# Blinds_Motor_ESP32.net
KiCad netlist of a schematic drawn in EAGLE
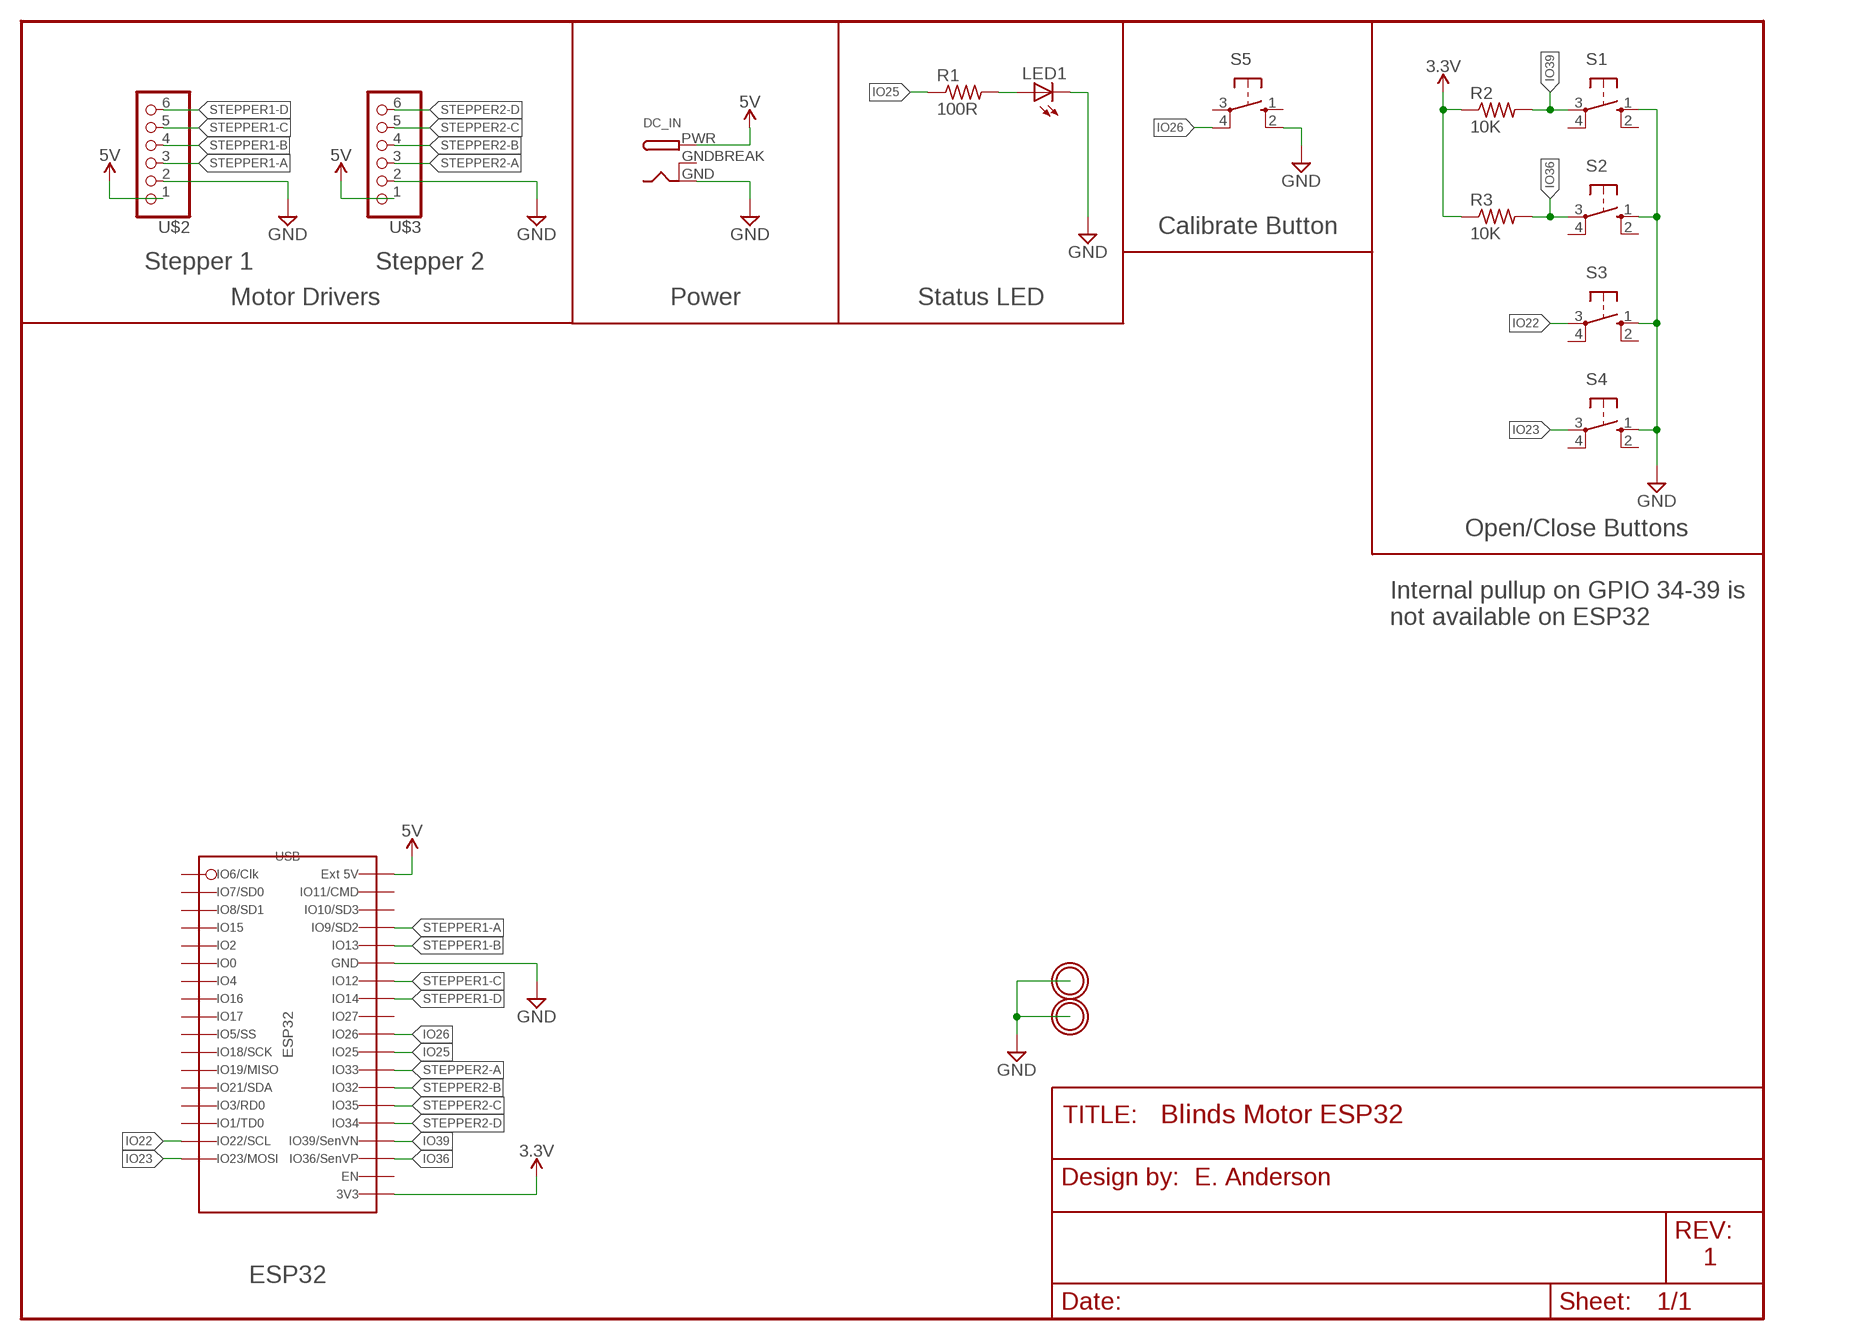
[diagram p0: schematic, sheet 1]

(export (version "E")
  (design (tool "Eeschema 10.0.6"))
  (components
    (comp (ref "DC_IN")
      (value "DCBARRELPTH")
      (footprint "eagle-import:DCJACK_2MM_PTH")
      (libsource (lib "eagle-import") (part "DCBARRELPTH"))
    )
    (comp (ref "LED1")
      (value "LED-CHIPLED_1206_LONG")
      (footprint "eagle-import:CHIPLED_1206_LONG")
      (libsource (lib "eagle-import") (part "LED-CHIPLED_1206_LONG"))
    )
    (comp (ref "R1")
      (value "100R")
      (footprint "eagle-import:R1206")
      (libsource (lib "eagle-import") (part "R_USR1206"))
    )
    (comp (ref "R2")
      (value "10K")
      (footprint "eagle-import:R1206")
      (libsource (lib "eagle-import") (part "R_USR1206"))
    )
    (comp (ref "R3")
      (value "10K")
      (footprint "eagle-import:R1206")
      (libsource (lib "eagle-import") (part "R_USR1206"))
    )
    (comp (ref "S1")
      (value "B3F-10XX")
      (footprint "eagle-import:B3F-10XX")
      (fields (field (name "MPN") "B3F-1000"))
      (libsource (lib "eagle-import") (part "B3F-10XX"))
    )
    (comp (ref "S2")
      (value "B3F-10XX")
      (footprint "eagle-import:B3F-10XX")
      (fields (field (name "MPN") "B3F-1000"))
      (libsource (lib "eagle-import") (part "B3F-10XX"))
    )
    (comp (ref "S3")
      (value "B3F-10XX")
      (footprint "eagle-import:B3F-10XX")
      (fields (field (name "MPN") "B3F-1000"))
      (libsource (lib "eagle-import") (part "B3F-10XX"))
    )
    (comp (ref "S4")
      (value "B3F-10XX")
      (footprint "eagle-import:B3F-10XX")
      (fields (field (name "MPN") "B3F-1000"))
      (libsource (lib "eagle-import") (part "B3F-10XX"))
    )
    (comp (ref "S5")
      (value "B3F-10XX")
      (footprint "eagle-import:B3F-10XX")
      (fields (field (name "MPN") "B3F-1000"))
      (libsource (lib "eagle-import") (part "B3F-10XX"))
    )
    (comp (ref "U$2")
      (value "Stepper 1")
      (footprint "eagle-import:1X06")
      (libsource (lib "eagle-import") (part "1X6_HEADER_LONG"))
    )
    (comp (ref "U$3")
      (value "Stepper 2")
      (footprint "eagle-import:1X06")
      (libsource (lib "eagle-import") (part "1X6_HEADER_LONG"))
    )
    (comp (ref "U$5")
      (value "MICROBUILDER_MOUNTINGHOLE3.0THIN")
      (footprint "eagle-import:MICROBUILDER_MOUNTINGHOLE_3.0_PLATEDTHIN")
      (libsource (lib "eagle-import") (part "MICROBUILDER_MOUNTINGHOLE3.0THIN"))
    )
    (comp (ref "U$6")
      (value "MICROBUILDER_MOUNTINGHOLE3.0THIN")
      (footprint "eagle-import:MICROBUILDER_MOUNTINGHOLE_3.0_PLATEDTHIN")
      (libsource (lib "eagle-import") (part "MICROBUILDER_MOUNTINGHOLE3.0THIN"))
    )
    (comp (ref "U$7")
      (value "ESP32-DEV")
      (footprint "eagle-import:ESP32_DEV")
      (libsource (lib "eagle-import") (part "ESP32-DEV"))
    )
  )
  (nets
    (net (code "1") (name "/GNDBREAK") (class "Default")
      (node (ref "DC_IN") (pin "GNDBREAK") (pinfunction "GNDBREAK_GNDBREAK") (pintype "power_in"))
    )
    (net (code "2") (name "3.3V") (class "Default")
      (node (ref "R2") (pin "1") (pinfunction "1_1") (pintype "passive"))
      (node (ref "R3") (pin "1") (pinfunction "1_1") (pintype "passive"))
      (node (ref "U$7") (pin "3V3") (pinfunction "3V3_3V3") (pintype "power_in"))
    )
    (net (code "3") (name "5V") (class "Default")
      (node (ref "DC_IN") (pin "PWR") (pinfunction "PWR_PWR") (pintype "power_in"))
      (node (ref "U$2") (pin "1") (pinfunction "1_1") (pintype "passive"))
      (node (ref "U$3") (pin "1") (pinfunction "1_1") (pintype "passive"))
      (node (ref "U$7") (pin "5V") (pinfunction "EXT_5V_5V") (pintype "power_in"))
    )
    (net (code "4") (name "GND") (class "Default")
      (node (ref "DC_IN") (pin "GND") (pinfunction "GND_GND") (pintype "power_in"))
      (node (ref "LED1") (pin "C") (pinfunction "C_C") (pintype "passive"))
      (node (ref "S1") (pin "1") (pinfunction "S_1") (pintype "passive"))
      (node (ref "S2") (pin "1") (pinfunction "S_1") (pintype "passive"))
      (node (ref "S3") (pin "1") (pinfunction "S_1") (pintype "passive"))
      (node (ref "S4") (pin "1") (pinfunction "S_1") (pintype "passive"))
      (node (ref "S5") (pin "2") (pinfunction "S1_2") (pintype "passive"))
      (node (ref "U$2") (pin "2") (pinfunction "2_2") (pintype "passive"))
      (node (ref "U$3") (pin "2") (pinfunction "2_2") (pintype "passive"))
      (node (ref "U$7") (pin "GND") (pinfunction "GND1_GND") (pintype "bidirectional"))
      (node (ref "U$7") (pin "GND1") (pinfunction "GND1_GND1") (pintype "bidirectional"))
      (node (ref "U$7") (pin "GND2") (pinfunction "GND1_GND2") (pintype "bidirectional"))
    )
    (net (code "5") (name "IO22") (class "Default")
      (node (ref "S3") (pin "3") (pinfunction "P_3") (pintype "passive"))
      (node (ref "U$7") (pin "IO22") (pinfunction "IO22_IO22") (pintype "bidirectional"))
    )
    (net (code "6") (name "IO23") (class "Default")
      (node (ref "S4") (pin "3") (pinfunction "P_3") (pintype "passive"))
      (node (ref "U$7") (pin "IO23") (pinfunction "IO23/SCL_IO23") (pintype "bidirectional"))
    )
    (net (code "7") (name "IO25") (class "Default")
      (node (ref "R1") (pin "1") (pinfunction "1_1") (pintype "passive"))
      (node (ref "U$7") (pin "IO25") (pinfunction "IO25_IO25") (pintype "bidirectional"))
    )
    (net (code "8") (name "IO26") (class "Default")
      (node (ref "S5") (pin "4") (pinfunction "P1_4") (pintype "passive"))
      (node (ref "U$7") (pin "IO26") (pinfunction "IO26_IO26") (pintype "bidirectional"))
    )
    (net (code "9") (name "IO36") (class "Default")
      (node (ref "R3") (pin "2") (pinfunction "2_2") (pintype "passive"))
      (node (ref "S2") (pin "3") (pinfunction "P_3") (pintype "passive"))
      (node (ref "U$7") (pin "IO36-SVP") (pinfunction "IO36/SVP_IO36-SVP") (pintype "bidirectional"))
    )
    (net (code "10") (name "IO39") (class "Default")
      (node (ref "R2") (pin "2") (pinfunction "2_2") (pintype "passive"))
      (node (ref "S1") (pin "3") (pinfunction "P_3") (pintype "passive"))
      (node (ref "U$7") (pin "IO39-SVN") (pinfunction "IO39/SVN_IO39-SVN") (pintype "bidirectional"))
    )
    (net (code "11") (name "Net-(LED1-PadA)") (class "Default")
      (node (ref "LED1") (pin "A") (pinfunction "A_A") (pintype "passive"))
      (node (ref "R1") (pin "2") (pinfunction "2_2") (pintype "passive"))
    )
    (net (code "12") (name "STEPPER1-A") (class "Default")
      (node (ref "U$2") (pin "3") (pinfunction "3_3") (pintype "passive"))
      (node (ref "U$7") (pin "IO9-SD2") (pinfunction "IO9/SD2_IO9-SD2") (pintype "bidirectional"))
    )
    (net (code "13") (name "STEPPER1-B") (class "Default")
      (node (ref "U$2") (pin "4") (pinfunction "4_4") (pintype "passive"))
      (node (ref "U$7") (pin "IO13") (pinfunction "IO13_IO13") (pintype "bidirectional"))
    )
    (net (code "14") (name "STEPPER1-C") (class "Default")
      (node (ref "U$2") (pin "5") (pinfunction "5_5") (pintype "passive"))
      (node (ref "U$7") (pin "IO12") (pinfunction "IO12_IO12") (pintype "bidirectional"))
    )
    (net (code "15") (name "STEPPER1-D") (class "Default")
      (node (ref "U$2") (pin "6") (pinfunction "6_6") (pintype "passive"))
      (node (ref "U$7") (pin "IO14") (pinfunction "IO14_IO14") (pintype "bidirectional"))
    )
    (net (code "16") (name "STEPPER2-A") (class "Default")
      (node (ref "U$3") (pin "3") (pinfunction "3_3") (pintype "passive"))
      (node (ref "U$7") (pin "IO33") (pinfunction "IO33_IO33") (pintype "bidirectional"))
    )
    (net (code "17") (name "STEPPER2-B") (class "Default")
      (node (ref "U$3") (pin "4") (pinfunction "4_4") (pintype "passive"))
      (node (ref "U$7") (pin "IO32") (pinfunction "IO32_IO32") (pintype "bidirectional"))
    )
    (net (code "18") (name "STEPPER2-C") (class "Default")
      (node (ref "U$3") (pin "5") (pinfunction "5_5") (pintype "passive"))
      (node (ref "U$7") (pin "IO35") (pinfunction "IO35_IO35") (pintype "bidirectional"))
    )
    (net (code "19") (name "STEPPER2-D") (class "Default")
      (node (ref "U$3") (pin "6") (pinfunction "6_6") (pintype "passive"))
      (node (ref "U$7") (pin "IO34") (pinfunction "IO34_IO34") (pintype "bidirectional"))
    )
    (net (code "20") (name "unconnected-(S1-P1-Pad4)") (class "Default")
      (node (ref "S1") (pin "4") (pinfunction "P1_4") (pintype "passive"))
    )
    (net (code "21") (name "unconnected-(S1-S1-Pad2)") (class "Default")
      (node (ref "S1") (pin "2") (pinfunction "S1_2") (pintype "passive"))
    )
    (net (code "22") (name "unconnected-(S2-P1-Pad4)") (class "Default")
      (node (ref "S2") (pin "4") (pinfunction "P1_4") (pintype "passive"))
    )
    (net (code "23") (name "unconnected-(S2-S1-Pad2)") (class "Default")
      (node (ref "S2") (pin "2") (pinfunction "S1_2") (pintype "passive"))
    )
    (net (code "24") (name "unconnected-(S3-P1-Pad4)") (class "Default")
      (node (ref "S3") (pin "4") (pinfunction "P1_4") (pintype "passive"))
    )
    (net (code "25") (name "unconnected-(S3-S1-Pad2)") (class "Default")
      (node (ref "S3") (pin "2") (pinfunction "S1_2") (pintype "passive"))
    )
    (net (code "26") (name "unconnected-(S4-P1-Pad4)") (class "Default")
      (node (ref "S4") (pin "4") (pinfunction "P1_4") (pintype "passive"))
    )
    (net (code "27") (name "unconnected-(S4-S1-Pad2)") (class "Default")
      (node (ref "S4") (pin "2") (pinfunction "S1_2") (pintype "passive"))
    )
    (net (code "28") (name "unconnected-(S5-P-Pad3)") (class "Default")
      (node (ref "S5") (pin "3") (pinfunction "P_3") (pintype "passive"))
    )
    (net (code "29") (name "unconnected-(S5-S-Pad1)") (class "Default")
      (node (ref "S5") (pin "1") (pinfunction "S_1") (pintype "passive"))
    )
    (net (code "30") (name "unconnected-(U$7-CLK-PadIO6-CLK)") (class "Default")
      (node (ref "U$7") (pin "IO6-CLK") (pinfunction "CLK_IO6-CLK") (pintype "bidirectional"))
    )
    (net (code "31") (name "unconnected-(U$7-IO10{slash}SD3-PadIO10-SD3)") (class "Default")
      (node (ref "U$7") (pin "IO10-SD3") (pinfunction "IO10/SD3_IO10-SD3") (pintype "bidirectional"))
    )
    (net (code "32") (name "unconnected-(U$7-IO11{slash}CMD-PadIO11-CMD)") (class "Default")
      (node (ref "U$7") (pin "IO11-CMD") (pinfunction "IO11/CMD_IO11-CMD") (pintype "bidirectional"))
    )
    (net (code "33") (name "unconnected-(U$7-IO21{slash}SDA-PadIO21)") (class "Default")
      (node (ref "U$7") (pin "IO21") (pinfunction "IO21/SDA_IO21") (pintype "bidirectional"))
    )
    (net (code "34") (name "unconnected-(U$7-PadEN)") (class "Default")
      (node (ref "U$7") (pin "EN") (pinfunction "EN_EN") (pintype "bidirectional"))
    )
    (net (code "35") (name "unconnected-(U$7-PadIO0)") (class "Default")
      (node (ref "U$7") (pin "IO0") (pinfunction "IO0_IO0") (pintype "bidirectional"))
    )
    (net (code "36") (name "unconnected-(U$7-PadIO2)") (class "Default")
      (node (ref "U$7") (pin "IO2") (pinfunction "IO2_IO2") (pintype "bidirectional"))
    )
    (net (code "37") (name "unconnected-(U$7-PadIO4)") (class "Default")
      (node (ref "U$7") (pin "IO4") (pinfunction "IO4_IO4") (pintype "bidirectional"))
    )
    (net (code "38") (name "unconnected-(U$7-PadIO5)") (class "Default")
      (node (ref "U$7") (pin "IO5") (pinfunction "IO5_IO5") (pintype "bidirectional"))
    )
    (net (code "39") (name "unconnected-(U$7-PadIO15)") (class "Default")
      (node (ref "U$7") (pin "IO15") (pinfunction "IO15_IO15") (pintype "bidirectional"))
    )
    (net (code "40") (name "unconnected-(U$7-PadIO16)") (class "Default")
      (node (ref "U$7") (pin "IO16") (pinfunction "IO16_IO16") (pintype "bidirectional"))
    )
    (net (code "41") (name "unconnected-(U$7-PadIO17)") (class "Default")
      (node (ref "U$7") (pin "IO17") (pinfunction "IO17_IO17") (pintype "bidirectional"))
    )
    (net (code "42") (name "unconnected-(U$7-PadIO18)") (class "Default")
      (node (ref "U$7") (pin "IO18") (pinfunction "IO18_IO18") (pintype "bidirectional"))
    )
    (net (code "43") (name "unconnected-(U$7-PadIO19)") (class "Default")
      (node (ref "U$7") (pin "IO19") (pinfunction "IO19_IO19") (pintype "bidirectional"))
    )
    (net (code "44") (name "unconnected-(U$7-PadIO27)") (class "Default")
      (node (ref "U$7") (pin "IO27") (pinfunction "IO27_IO27") (pintype "bidirectional"))
    )
    (net (code "45") (name "unconnected-(U$7-RXD0-PadIO3-RXD0)") (class "Default")
      (node (ref "U$7") (pin "IO3-RXD0") (pinfunction "RXD0_IO3-RXD0") (pintype "input"))
    )
    (net (code "46") (name "unconnected-(U$7-SD0-PadIO7-SD0)") (class "Default")
      (node (ref "U$7") (pin "IO7-SD0") (pinfunction "SD0_IO7-SD0") (pintype "bidirectional"))
    )
    (net (code "47") (name "unconnected-(U$7-SD1-PadIO8-SD1)") (class "Default")
      (node (ref "U$7") (pin "IO8-SD1") (pinfunction "SD1_IO8-SD1") (pintype "bidirectional"))
    )
    (net (code "48") (name "unconnected-(U$7-TXD0-PadIO1-TXD0)") (class "Default")
      (node (ref "U$7") (pin "IO1-TXD0") (pinfunction "TXD0_IO1-TXD0") (pintype "output"))
    )
  )
)
